# LEDs_v1.net
KiCad netlist of a schematic drawn in EAGLE
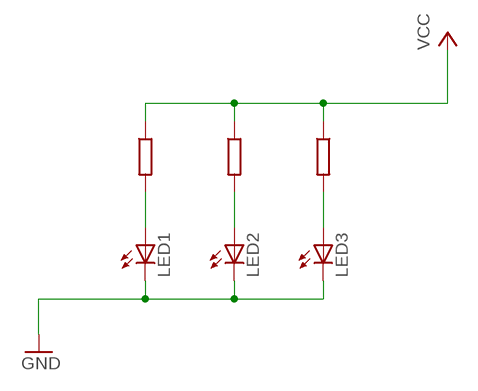
[diagram p0: schematic, sheet 1]

(export (version "E")
  (design (tool "Eeschema 10.0.6"))
  (components
    (comp (ref "LED1")
      (value "LED")
      (footprint "eagle-import:SMARTLED-TTW")
      (libsource (lib "eagle-import") (part "LED"))
    )
    (comp (ref "LED2")
      (value "LED")
      (footprint "eagle-import:SMARTLED-TTW")
      (libsource (lib "eagle-import") (part "LED"))
    )
    (comp (ref "LED3")
      (value "LED")
      (footprint "eagle-import:SMARTLED-TTW")
      (libsource (lib "eagle-import") (part "LED"))
    )
  )
  (nets
    (net (code "1") (name "GND") (class "Default")
      (node (ref "LED1") (pin "C@1") (pinfunction "C_C@1") (pintype "passive"))
      (node (ref "LED2") (pin "C@1") (pinfunction "C_C@1") (pintype "passive"))
      (node (ref "LED3") (pin "C@1") (pinfunction "C_C@1") (pintype "passive"))
    )
    (net (code "3") (name "unconnected-(LED1-A-PadA@1)") (class "Default")
      (node (ref "LED1") (pin "A@1") (pinfunction "A_A@1") (pintype "passive"))
    )
    (net (code "4") (name "unconnected-(LED2-A-PadA@1)") (class "Default")
      (node (ref "LED2") (pin "A@1") (pinfunction "A_A@1") (pintype "passive"))
    )
    (net (code "5") (name "unconnected-(LED3-A-PadA@1)") (class "Default")
      (node (ref "LED3") (pin "A@1") (pinfunction "A_A@1") (pintype "passive"))
    )
  )
)
